# AUDIO-AMPLIFIER.net
KiCad netlist of a schematic drawn in Altium Designer
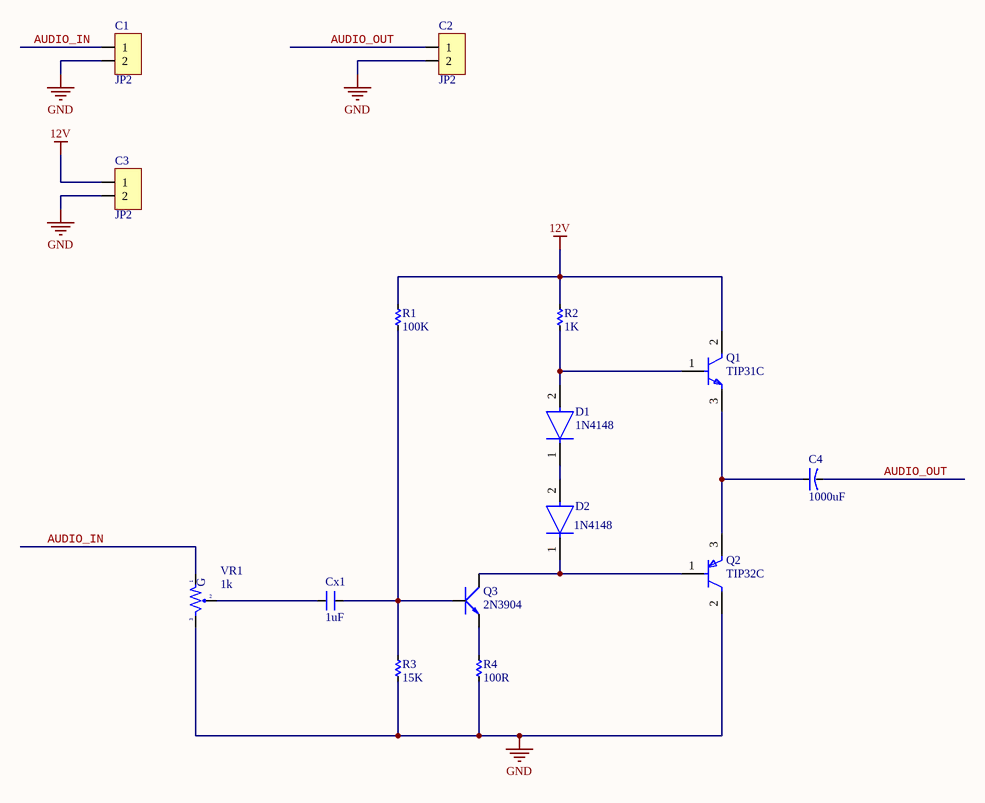
[diagram p0: AUDIO-AMPLIFIER.SchDoc]

(export (version "E")
  (design (tool "Eeschema 10.0.6"))
  (components
    (comp (ref "C1")
      (value "JP2")
      (footprint "JP2-D1T")
      (description "WR-PHD 2.54 mm Angled Socket Header")
      (fields
        (field (name "MANUFACTURER") "Würth Elektronik eiSos GmbH")
        (field (name "PARTNO") "613002143121")
        (field (name "CREATED BY") "Karrer Zheng")
      )
      (libsource (lib "LIBRARY_MuaLinhKien") (part "JP2"))
    )
    (comp (ref "C2")
      (value "JP2")
      (footprint "JP2-D1T")
      (description "WR-PHD 2.54 mm Angled Socket Header")
      (fields
        (field (name "MANUFACTURER") "Würth Elektronik eiSos GmbH")
        (field (name "PARTNO") "613002143121")
        (field (name "CREATED BY") "Karrer Zheng")
      )
      (libsource (lib "LIBRARY_MuaLinhKien") (part "JP2"))
    )
    (comp (ref "C3")
      (value "JP2")
      (footprint "JP2-D1T")
      (description "WR-PHD 2.54 mm Angled Socket Header")
      (fields
        (field (name "MANUFACTURER") "Würth Elektronik eiSos GmbH")
        (field (name "PARTNO") "613002143121")
        (field (name "CREATED BY") "Karrer Zheng")
      )
      (libsource (lib "LIBRARY_MuaLinhKien") (part "JP2"))
    )
    (comp (ref "C4")
      (value "1000uF")
      (footprint "CA-ALU-16")
      (description "Capacitor (Semiconductor SIM Model)")
      (fields (field (name "PUBLISHER") "Altium Limited"))
      (libsource (lib "LIBRARY_MuaLinhKien") (part "CN-ALU-DIP"))
    )
    (comp (ref "Cx1") (value "1uF") (footprint "CN1.5") (libsource (lib "LIBRARY_MuaLinhKien") (part "CN")))
    (comp (ref "D1")
      (value "1N4148")
      (footprint "FP-017AG-MFG")
      (description "DIODE GEN PURP 100V 200MA DO35")
      (fields (field (name "VOLTAGE") "100V"))
      (libsource (lib "Altium Content Vault") (part "d7152d700b627762746794eb795d46e"))
    )
    (comp (ref "D2")
      (value "1N4148")
      (footprint "FP-017AG-MFG")
      (description "DIODE GEN PURP 100V 200MA DO35")
      (fields (field (name "VOLTAGE") "100V"))
      (libsource (lib "Altium Content Vault") (part "d7152d700b627762746794eb795d46e"))
    )
    (comp (ref "Q1")
      (value "TIP31C")
      (footprint "FP-TO-220-P0A0015988-MFG")
      (description "TRANS NPN 100V 3A TO-220")
      (fields
        (field (name "OCTOPART") "https://octopart.com/tip31c-stmicroelectronics-15555")
        (field (name "MANUFACTURER") "STMicroelectronics")
      )
      (libsource (lib "Altium Content Vault") (part "1c57d9dae74fe2702546667b0e849db"))
    )
    (comp (ref "Q2")
      (value "TIP32C")
      (footprint "FP-TO-220-P0A0015988-MFG")
      (description "TRANS PNP 100V 3A TO-220")
      (fields
        (field (name "MANUFACTURER") "STMicroelectronics")
        (field (name "OCTOPART") "https://octopart.com/tip32c-stmicroelectronics-353617")
      )
      (libsource (lib "Altium Content Vault") (part "802a31d42ca070764d097f06bc9597f"))
    )
    (comp (ref "Q3")
      (value "2N3904")
      (footprint "TO92-123")
      (description "NPN 600mW, ECB")
      (libsource (lib "LIBRARY_MuaLinhKien") (part "2N904"))
    )
    (comp (ref "R1")
      (value "100K")
      (footprint "RES-1/4W")
      (description "Res")
      (fields
        (field (name "MANUFACTURER") "Generic Components")
        (field (name "PUBLISHER") "Altium Hobart Technology Centre")
      )
      (libsource (lib "LIBRARY_MuaLinhKien") (part "Res"))
    )
    (comp (ref "R2")
      (value "1K")
      (footprint "RES-1/4W")
      (description "Res")
      (fields
        (field (name "MANUFACTURER") "Generic Components")
        (field (name "PUBLISHER") "Altium Hobart Technology Centre")
      )
      (libsource (lib "LIBRARY_MuaLinhKien") (part "Res"))
    )
    (comp (ref "R3")
      (value "15K")
      (footprint "RES-1/4W")
      (description "Res")
      (fields
        (field (name "MANUFACTURER") "Generic Components")
        (field (name "PUBLISHER") "Altium Hobart Technology Centre")
      )
      (libsource (lib "LIBRARY_MuaLinhKien") (part "Res"))
    )
    (comp (ref "R4")
      (value "100R")
      (footprint "RES-1/4W")
      (description "Res")
      (fields
        (field (name "MANUFACTURER") "Generic Components")
        (field (name "PUBLISHER") "Altium Hobart Technology Centre")
      )
      (libsource (lib "LIBRARY_MuaLinhKien") (part "Res"))
    )
    (comp (ref "VR1")
      (value "1k")
      (footprint "VR-S1")
      (description "Var Resistor")
      (libsource (lib "LIBRARY_MuaLinhKien") (part "VR-S"))
    )
  )
  (nets
    (net (code "1") (name "/AUDIO_IN") (class "Default")
      (node (ref "C1") (pin "1") (pinfunction "1_1") (pintype "passive"))
      (node (ref "VR1") (pin "1") (pinfunction "1_1") (pintype "passive"))
    )
    (net (code "2") (name "/AUDIO_OUT") (class "Default")
      (node (ref "C2") (pin "1") (pinfunction "1_1") (pintype "passive"))
      (node (ref "C4") (pin "2") (pinfunction "2_2") (pintype "passive"))
    )
    (net (code "3") (name "12V") (class "Default")
      (node (ref "C3") (pin "1") (pinfunction "1_1") (pintype "passive"))
      (node (ref "Q1") (pin "2") (pinfunction "C_2") (pintype "passive"))
      (node (ref "R1") (pin "1") (pinfunction "1_1") (pintype "passive"))
      (node (ref "R2") (pin "1") (pinfunction "1_1") (pintype "passive"))
    )
    (net (code "4") (name "GND") (class "Default")
      (node (ref "C1") (pin "2") (pinfunction "2_2") (pintype "passive"))
      (node (ref "C2") (pin "2") (pinfunction "2_2") (pintype "passive"))
      (node (ref "C3") (pin "2") (pinfunction "2_2") (pintype "passive"))
      (node (ref "Q2") (pin "2") (pinfunction "C_2") (pintype "passive"))
      (node (ref "R3") (pin "2") (pinfunction "2_2") (pintype "passive"))
      (node (ref "R4") (pin "2") (pinfunction "2_2") (pintype "passive"))
      (node (ref "VR1") (pin "3") (pinfunction "3_3") (pintype "passive"))
    )
    (net (code "5") (name "Net-(Cx1-Pad1)") (class "Default")
      (node (ref "Cx1") (pin "1") (pinfunction "1_1") (pintype "passive"))
      (node (ref "VR1") (pin "2") (pinfunction "2_2") (pintype "passive"))
    )
    (net (code "6") (name "Net-(D1-A)") (class "Default")
      (node (ref "D1") (pin "2") (pinfunction "A_2") (pintype "passive"))
      (node (ref "Q1") (pin "1") (pinfunction "B_1") (pintype "passive"))
      (node (ref "R2") (pin "2") (pinfunction "2_2") (pintype "passive"))
    )
    (net (code "7") (name "Net-(D1-C)") (class "Default")
      (node (ref "D1") (pin "1") (pinfunction "C_1") (pintype "passive"))
      (node (ref "D2") (pin "2") (pinfunction "A_2") (pintype "passive"))
    )
    (net (code "8") (name "Net-(D2-C)") (class "Default")
      (node (ref "D2") (pin "1") (pinfunction "C_1") (pintype "passive"))
      (node (ref "Q2") (pin "1") (pinfunction "B_1") (pintype "passive"))
      (node (ref "Q3") (pin "3") (pinfunction "C_3") (pintype "passive"))
    )
    (net (code "9") (name "Net-(Q1-E)") (class "Default")
      (node (ref "C4") (pin "1") (pinfunction "1_1") (pintype "passive"))
      (node (ref "Q1") (pin "3") (pinfunction "E_3") (pintype "passive"))
      (node (ref "Q2") (pin "3") (pinfunction "E_3") (pintype "passive"))
    )
    (net (code "10") (name "Net-(Q3-B)") (class "Default")
      (node (ref "Cx1") (pin "2") (pinfunction "2_2") (pintype "passive"))
      (node (ref "Q3") (pin "2") (pinfunction "B_2") (pintype "passive"))
      (node (ref "R1") (pin "2") (pinfunction "2_2") (pintype "passive"))
      (node (ref "R3") (pin "1") (pinfunction "1_1") (pintype "passive"))
    )
    (net (code "11") (name "Net-(Q3-E)") (class "Default")
      (node (ref "Q3") (pin "1") (pinfunction "E_1") (pintype "passive"))
      (node (ref "R4") (pin "1") (pinfunction "1_1") (pintype "passive"))
    )
  )
)
